# 555-schematic.net
KiCad netlist of a schematic drawn in Altium Designer
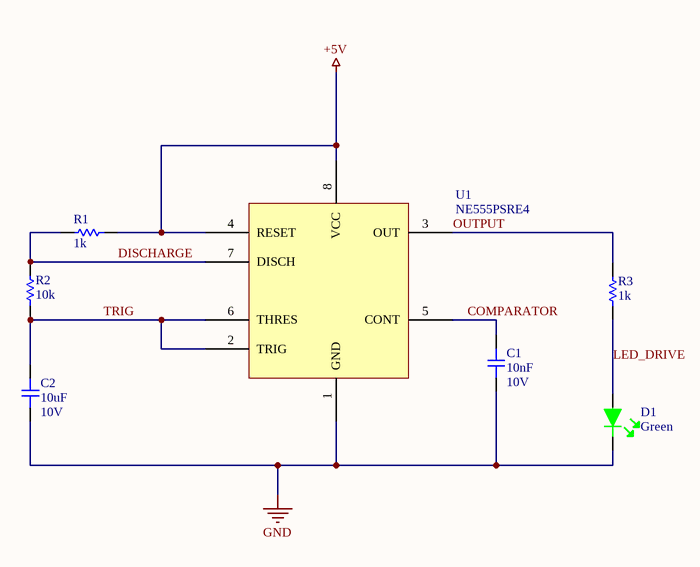
[diagram p0: 555-schematic.SchDoc]

(export (version "E")
  (design (tool "Eeschema 10.0.6"))
  (components
    (comp (ref "C1")
      (value "10nF")
      (footprint "C603")
      (description "Cap Ceramic 0.01uF 10V X7R 10% SMD 0603 125C Paper T/R")
      (fields
        (field (name "MANUFACTURER") "Yageo")
        (field (name "MANUFACTURER PART NUMBER") "CC0603KRX7R6BB103")
        (field (name "VOLTAGE RATING (DC)") "10V")
      )
      (libsource (lib "Schlib1") (part "CC0603KRX7R6BB103"))
    )
    (comp (ref "C2")
      (value "10uF")
      (footprint "C603")
      (description "CAPACITOR, 0805, X6S, 10V, 10UF")
      (fields
        (field (name "MANUFACTURER") "Murata")
        (field (name "MANUFACTURER PART NUMBER") "GRM21BC81A106KE18L")
        (field (name "VOLTAGE") "10V")
      )
      (libsource (lib "Schlib1") (part "GRM21BC81A106KE18L"))
    )
    (comp (ref "D1")
      (value "Green")
      (footprint "LED_0603")
      (description "Green 0805 130 º Min 5 mcd Typical 12 mcd Water Clear Lens SMT LED")
      (fields
        (field (name "MANUFACTURER") "Vishay Lite-On")
        (field (name "MANUFACTURER PART NUMBER") "LTST-C171GKT")
      )
      (libsource (lib "Schlib1") (part "LTST-C171GKT"))
    )
    (comp (ref "R1")
      (value "1k")
      (footprint "R0603")
      (fields
        (field (name "MANUFACTURER") "Rohm")
        (field (name "MANUFACTURER PART NUMBER") "ESR03EZPJ102")
        (field (name "TOLERANCE") "5%")
      )
      (libsource (lib "Schlib1") (part "ESR03EZPJ102"))
    )
    (comp (ref "R2")
      (value "10k")
      (footprint "R0603")
      (description "Res Thick Film 0603 10K Ohm 5% 1/10W ±100ppm/°C Molded SMD SMD Paper T/R")
      (fields
        (field (name "MANUFACTURER") "Stackpole Electronics")
        (field (name "MANUFACTURER PART NUMBER") "RMCF0603JT10K0")
      )
      (libsource (lib "Schlib1") (part "RMCF0603JT10K0"))
    )
    (comp (ref "R3")
      (value "1k")
      (footprint "R0603")
      (fields
        (field (name "MANUFACTURER") "Rohm")
        (field (name "MANUFACTURER PART NUMBER") "ESR03EZPJ102")
        (field (name "TOLERANCE") "5%")
      )
      (libsource (lib "Schlib1") (part "ESR03EZPJ102"))
    )
    (comp (ref "U1")
      (value "NE555PSRE4")
      (footprint "SOIC-8")
      (description "IC OSC SINGLE TIMER 100KHZ 8SO")
      (fields (field (name "MANUFACTURER") "Texas Instruments"))
      (libsource (lib "Schlib1") (part "NE555PSRE4"))
    )
  )
  (nets
    (net (code "1") (name "+5V") (class "Default")
      (node (ref "R1") (pin "1") (pinfunction "1_1") (pintype "passive"))
      (node (ref "U1") (pin "4") (pinfunction "RESET_4") (pintype "passive"))
      (node (ref "U1") (pin "8") (pinfunction "VCC_8") (pintype "passive"))
    )
    (net (code "2") (name "/COMPARATOR") (class "Default")
      (node (ref "C1") (pin "2") (pinfunction "2_2") (pintype "passive"))
      (node (ref "U1") (pin "5") (pinfunction "CONT_5") (pintype "passive"))
    )
    (net (code "3") (name "/DISCHARGE") (class "Default")
      (node (ref "R1") (pin "2") (pinfunction "2_2") (pintype "passive"))
      (node (ref "R2") (pin "2") (pinfunction "2_2") (pintype "passive"))
      (node (ref "U1") (pin "7") (pinfunction "DISCH_7") (pintype "passive"))
    )
    (net (code "4") (name "/LED_DRIVE") (class "Default")
      (node (ref "D1") (pin "1") (pinfunction "1_1") (pintype "passive"))
      (node (ref "R3") (pin "1") (pinfunction "1_1") (pintype "passive"))
    )
    (net (code "5") (name "/OUTPUT") (class "Default")
      (node (ref "R3") (pin "2") (pinfunction "2_2") (pintype "passive"))
      (node (ref "U1") (pin "3") (pinfunction "OUT_3") (pintype "passive"))
    )
    (net (code "6") (name "/TRIG") (class "Default")
      (node (ref "C2") (pin "2") (pinfunction "2_2") (pintype "passive"))
      (node (ref "R2") (pin "1") (pinfunction "1_1") (pintype "passive"))
      (node (ref "U1") (pin "2") (pinfunction "TRIG_2") (pintype "passive"))
      (node (ref "U1") (pin "6") (pinfunction "THRES_6") (pintype "passive"))
    )
    (net (code "7") (name "GND") (class "Default")
      (node (ref "C1") (pin "1") (pinfunction "1_1") (pintype "passive"))
      (node (ref "C2") (pin "1") (pinfunction "1_1") (pintype "passive"))
      (node (ref "D1") (pin "2") (pinfunction "2_2") (pintype "passive"))
      (node (ref "U1") (pin "1") (pinfunction "GND_1") (pintype "passive"))
    )
  )
)
